# ps3.net
KiCad netlist of a schematic drawn in EAGLE
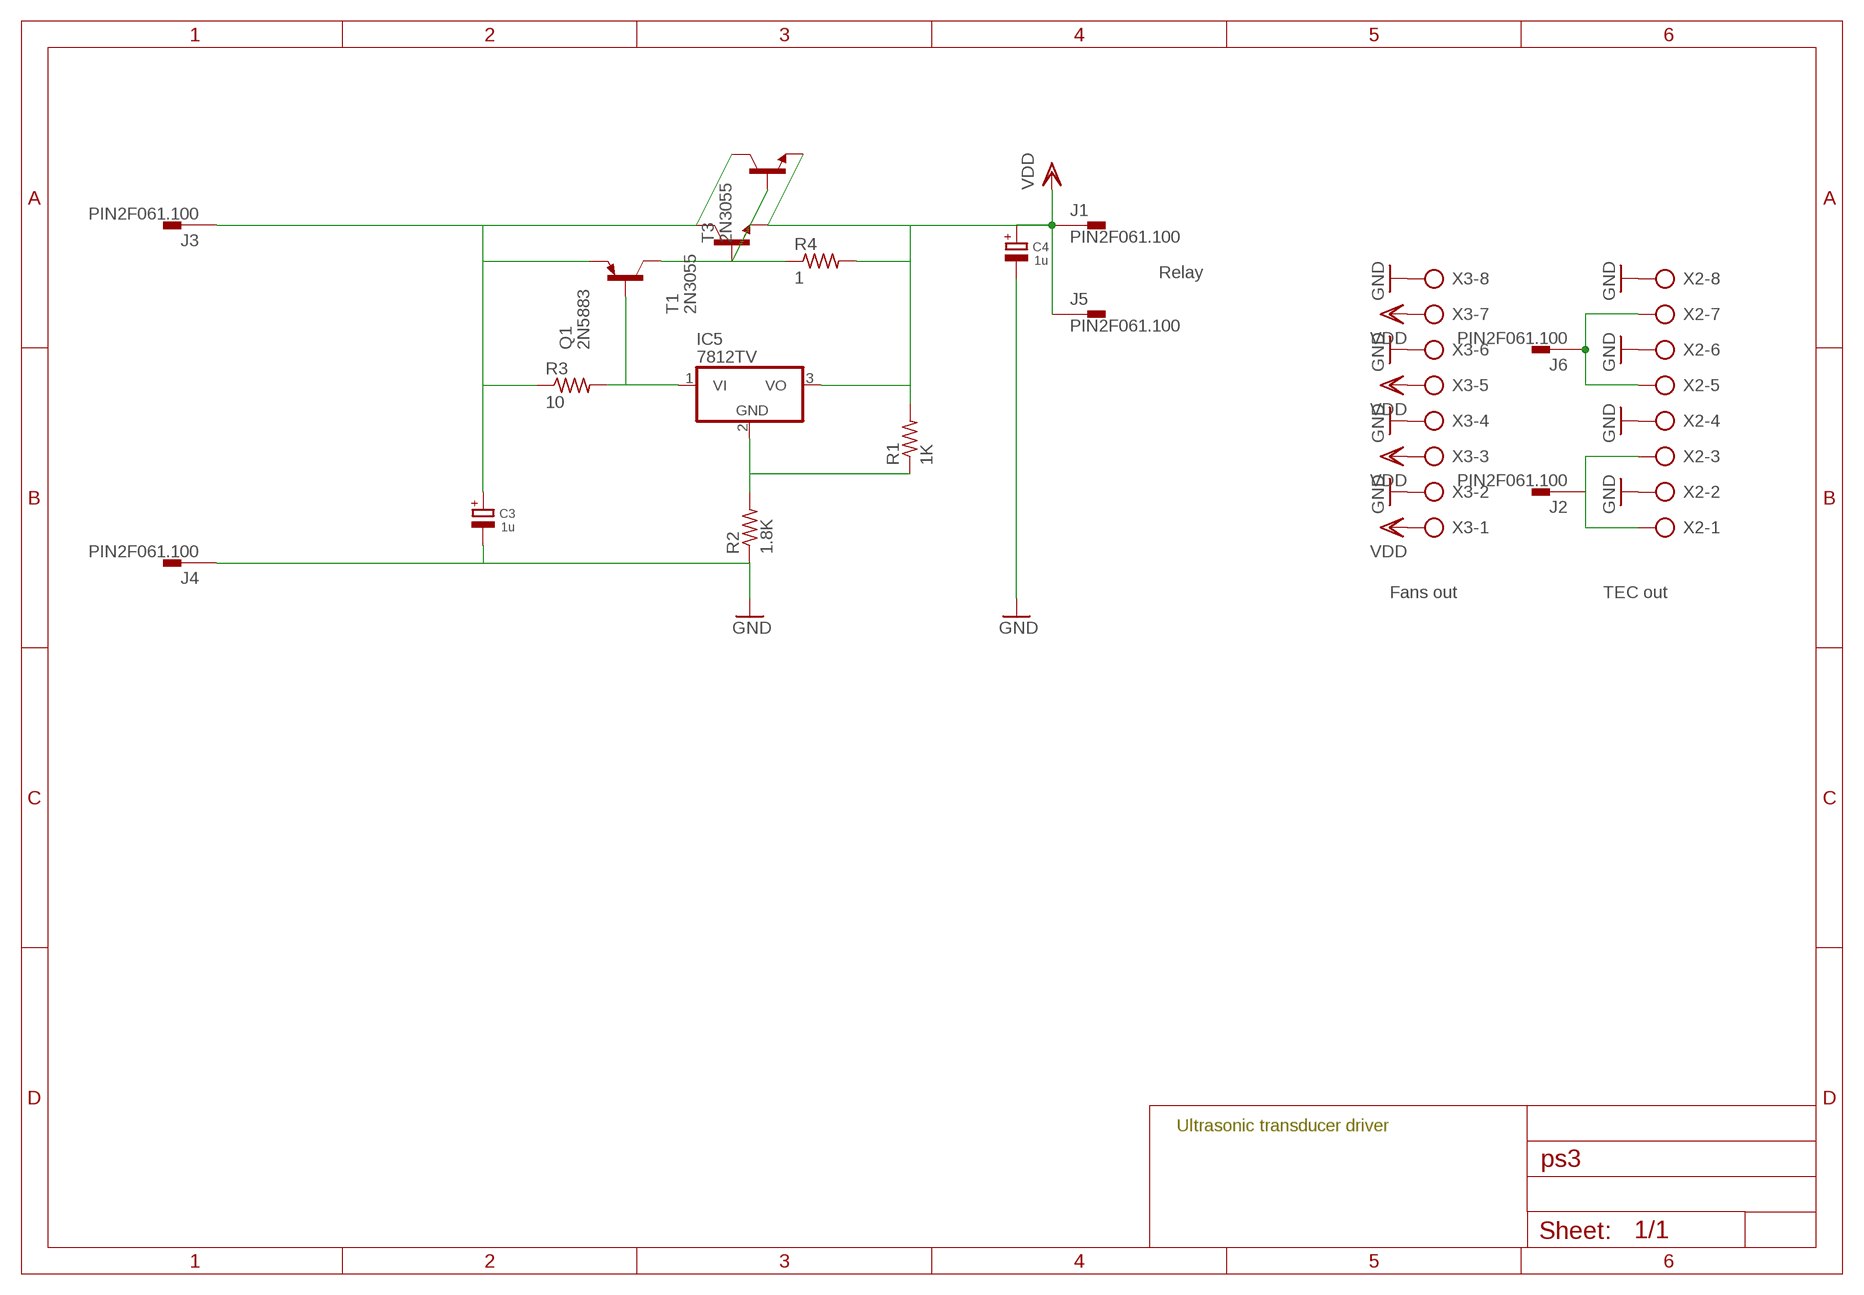
[diagram p0: schematic, sheet 1]

(export (version "E")
  (design (tool "Eeschema 10.0.6"))
  (components
    (comp (ref "C3")
      (value "1u")
      (footprint "eagle-import:EB20D")
      (libsource (lib "eagle-import") (part "CPOL-EUE10-20"))
    )
    (comp (ref "C4")
      (value "1u")
      (footprint "eagle-import:EB20D")
      (libsource (lib "eagle-import") (part "CPOL-EUE10-20"))
    )
    (comp (ref "IC5")
      (value "7812TV")
      (footprint "eagle-import:TO220V")
      (libsource (lib "eagle-import") (part "78TV12"))
    )
    (comp (ref "J1")
      (value "PIN2F061.100")
      (footprint "eagle-import:F061.100")
      (libsource (lib "eagle-import") (part "PIN2F061.100"))
    )
    (comp (ref "J2")
      (value "PIN2F061.100")
      (footprint "eagle-import:F061.100")
      (libsource (lib "eagle-import") (part "PIN2F061.100"))
    )
    (comp (ref "J3")
      (value "PIN2F061.100")
      (footprint "eagle-import:F061.100")
      (libsource (lib "eagle-import") (part "PIN2F061.100"))
    )
    (comp (ref "J4")
      (value "PIN2F061.100")
      (footprint "eagle-import:F061.100")
      (libsource (lib "eagle-import") (part "PIN2F061.100"))
    )
    (comp (ref "J5")
      (value "PIN2F061.100")
      (footprint "eagle-import:F061.100")
      (libsource (lib "eagle-import") (part "PIN2F061.100"))
    )
    (comp (ref "J6")
      (value "PIN2F061.100")
      (footprint "eagle-import:F061.100")
      (libsource (lib "eagle-import") (part "PIN2F061.100"))
    )
    (comp (ref "Q1")
      (value "2N5883")
      (footprint "eagle-import:TO3")
      (libsource (lib "eagle-import") (part "2N4905"))
    )
    (comp (ref "R1")
      (value "1K")
      (footprint "eagle-import:0207_15")
      (libsource (lib "eagle-import") (part "R-US_0207/15"))
    )
    (comp (ref "R2")
      (value "1.8K")
      (footprint "eagle-import:0207_15")
      (libsource (lib "eagle-import") (part "R-US_0207/15"))
    )
    (comp (ref "R3")
      (value "10")
      (footprint "eagle-import:0207_15")
      (libsource (lib "eagle-import") (part "R-US_0207/15"))
    )
    (comp (ref "R4")
      (value "1")
      (footprint "eagle-import:0922_22")
      (libsource (lib "eagle-import") (part "R-US_0922/22"))
    )
    (comp (ref "T1")
      (value "2N3055")
      (footprint "eagle-import:TO3")
      (libsource (lib "eagle-import") (part "2N3055"))
    )
    (comp (ref "T3")
      (value "2N3055")
      (footprint "eagle-import:TO3")
      (libsource (lib "eagle-import") (part "2N3055"))
    )
    (comp (ref "X2")
      (value "AK300/8")
      (footprint "eagle-import:AK300_8")
      (libsource (lib "eagle-import") (part "AK300/8"))
    )
    (comp (ref "X3")
      (value "AK300/8")
      (footprint "eagle-import:AK300_8")
      (libsource (lib "eagle-import") (part "AK300/8"))
    )
  )
  (nets
    (net (code "1") (name "GND") (class "Default")
      (node (ref "C3") (pin "-") (pinfunction "-_-") (pintype "passive"))
      (node (ref "C4") (pin "-") (pinfunction "-_-") (pintype "passive"))
      (node (ref "J4") (pin "A1") (pinfunction "1_A1") (pintype "passive"))
      (node (ref "J4") (pin "A2") (pinfunction "1_A2") (pintype "passive"))
      (node (ref "R2") (pin "1") (pinfunction "1_1") (pintype "passive"))
      (node (ref "X2") (pin "2") (pinfunction "KL_2") (pintype "passive"))
      (node (ref "X2") (pin "4") (pinfunction "KL_4") (pintype "passive"))
      (node (ref "X2") (pin "6") (pinfunction "KL_6") (pintype "passive"))
      (node (ref "X2") (pin "8") (pinfunction "KL_8") (pintype "passive"))
      (node (ref "X3") (pin "2") (pinfunction "KL_2") (pintype "passive"))
      (node (ref "X3") (pin "4") (pinfunction "KL_4") (pintype "passive"))
      (node (ref "X3") (pin "6") (pinfunction "KL_6") (pintype "passive"))
      (node (ref "X3") (pin "8") (pinfunction "KL_8") (pintype "passive"))
    )
    (net (code "2") (name "Net-(C3-Pad+)") (class "Default")
      (node (ref "C3") (pin "+") (pinfunction "+_+") (pintype "passive"))
      (node (ref "J3") (pin "A1") (pinfunction "1_A1") (pintype "passive"))
      (node (ref "J3") (pin "A2") (pinfunction "1_A2") (pintype "passive"))
      (node (ref "Q1") (pin "E") (pinfunction "E_E") (pintype "passive"))
      (node (ref "R3") (pin "1") (pinfunction "1_1") (pintype "passive"))
      (node (ref "T1") (pin "C") (pinfunction "C_C") (pintype "passive"))
      (node (ref "T1") (pin "C/") (pinfunction "C_C/") (pintype "passive"))
      (node (ref "T3") (pin "C") (pinfunction "C_C") (pintype "passive"))
      (node (ref "T3") (pin "C/") (pinfunction "C_C/") (pintype "passive"))
    )
    (net (code "3") (name "Net-(IC5-GND)") (class "Default")
      (node (ref "IC5") (pin "2") (pinfunction "GND_2") (pintype "passive"))
      (node (ref "R1") (pin "1") (pinfunction "1_1") (pintype "passive"))
      (node (ref "R2") (pin "2") (pinfunction "2_2") (pintype "passive"))
    )
    (net (code "4") (name "Net-(IC5-VI)") (class "Default")
      (node (ref "IC5") (pin "1") (pinfunction "VI_1") (pintype "input"))
      (node (ref "Q1") (pin "B") (pinfunction "B_B") (pintype "passive"))
      (node (ref "R3") (pin "2") (pinfunction "2_2") (pintype "passive"))
    )
    (net (code "5") (name "Net-(Q1-C-PadC{slash})") (class "Default")
      (node (ref "Q1") (pin "C") (pinfunction "C_C") (pintype "passive"))
      (node (ref "Q1") (pin "C/") (pinfunction "C_C/") (pintype "passive"))
      (node (ref "R4") (pin "1") (pinfunction "1_1") (pintype "passive"))
      (node (ref "T1") (pin "B") (pinfunction "B_B") (pintype "passive"))
      (node (ref "T3") (pin "B") (pinfunction "B_B") (pintype "passive"))
    )
    (net (code "6") (name "Net-(X2A-KL)") (class "Default")
      (node (ref "J2") (pin "A1") (pinfunction "1_A1") (pintype "passive"))
      (node (ref "J2") (pin "A2") (pinfunction "1_A2") (pintype "passive"))
      (node (ref "X2") (pin "1") (pinfunction "KL_1") (pintype "passive"))
      (node (ref "X2") (pin "3") (pinfunction "KL_3") (pintype "passive"))
    )
    (net (code "7") (name "Net-(X2E-KL)") (class "Default")
      (node (ref "J6") (pin "A1") (pinfunction "1_A1") (pintype "passive"))
      (node (ref "J6") (pin "A2") (pinfunction "1_A2") (pintype "passive"))
      (node (ref "X2") (pin "5") (pinfunction "KL_5") (pintype "passive"))
      (node (ref "X2") (pin "7") (pinfunction "KL_7") (pintype "passive"))
    )
    (net (code "8") (name "VDD") (class "Default")
      (node (ref "C4") (pin "+") (pinfunction "+_+") (pintype "passive"))
      (node (ref "IC5") (pin "3") (pinfunction "VO_3") (pintype "passive"))
      (node (ref "J1") (pin "A1") (pinfunction "1_A1") (pintype "passive"))
      (node (ref "J1") (pin "A2") (pinfunction "1_A2") (pintype "passive"))
      (node (ref "J5") (pin "A1") (pinfunction "1_A1") (pintype "passive"))
      (node (ref "J5") (pin "A2") (pinfunction "1_A2") (pintype "passive"))
      (node (ref "R1") (pin "2") (pinfunction "2_2") (pintype "passive"))
      (node (ref "R4") (pin "2") (pinfunction "2_2") (pintype "passive"))
      (node (ref "T1") (pin "E") (pinfunction "E_E") (pintype "passive"))
      (node (ref "T3") (pin "E") (pinfunction "E_E") (pintype "passive"))
      (node (ref "X3") (pin "1") (pinfunction "KL_1") (pintype "passive"))
      (node (ref "X3") (pin "3") (pinfunction "KL_3") (pintype "passive"))
      (node (ref "X3") (pin "5") (pinfunction "KL_5") (pintype "passive"))
      (node (ref "X3") (pin "7") (pinfunction "KL_7") (pintype "passive"))
    )
  )
)
